# RemoteControl-v3.net
KiCad netlist of a schematic drawn in EAGLE
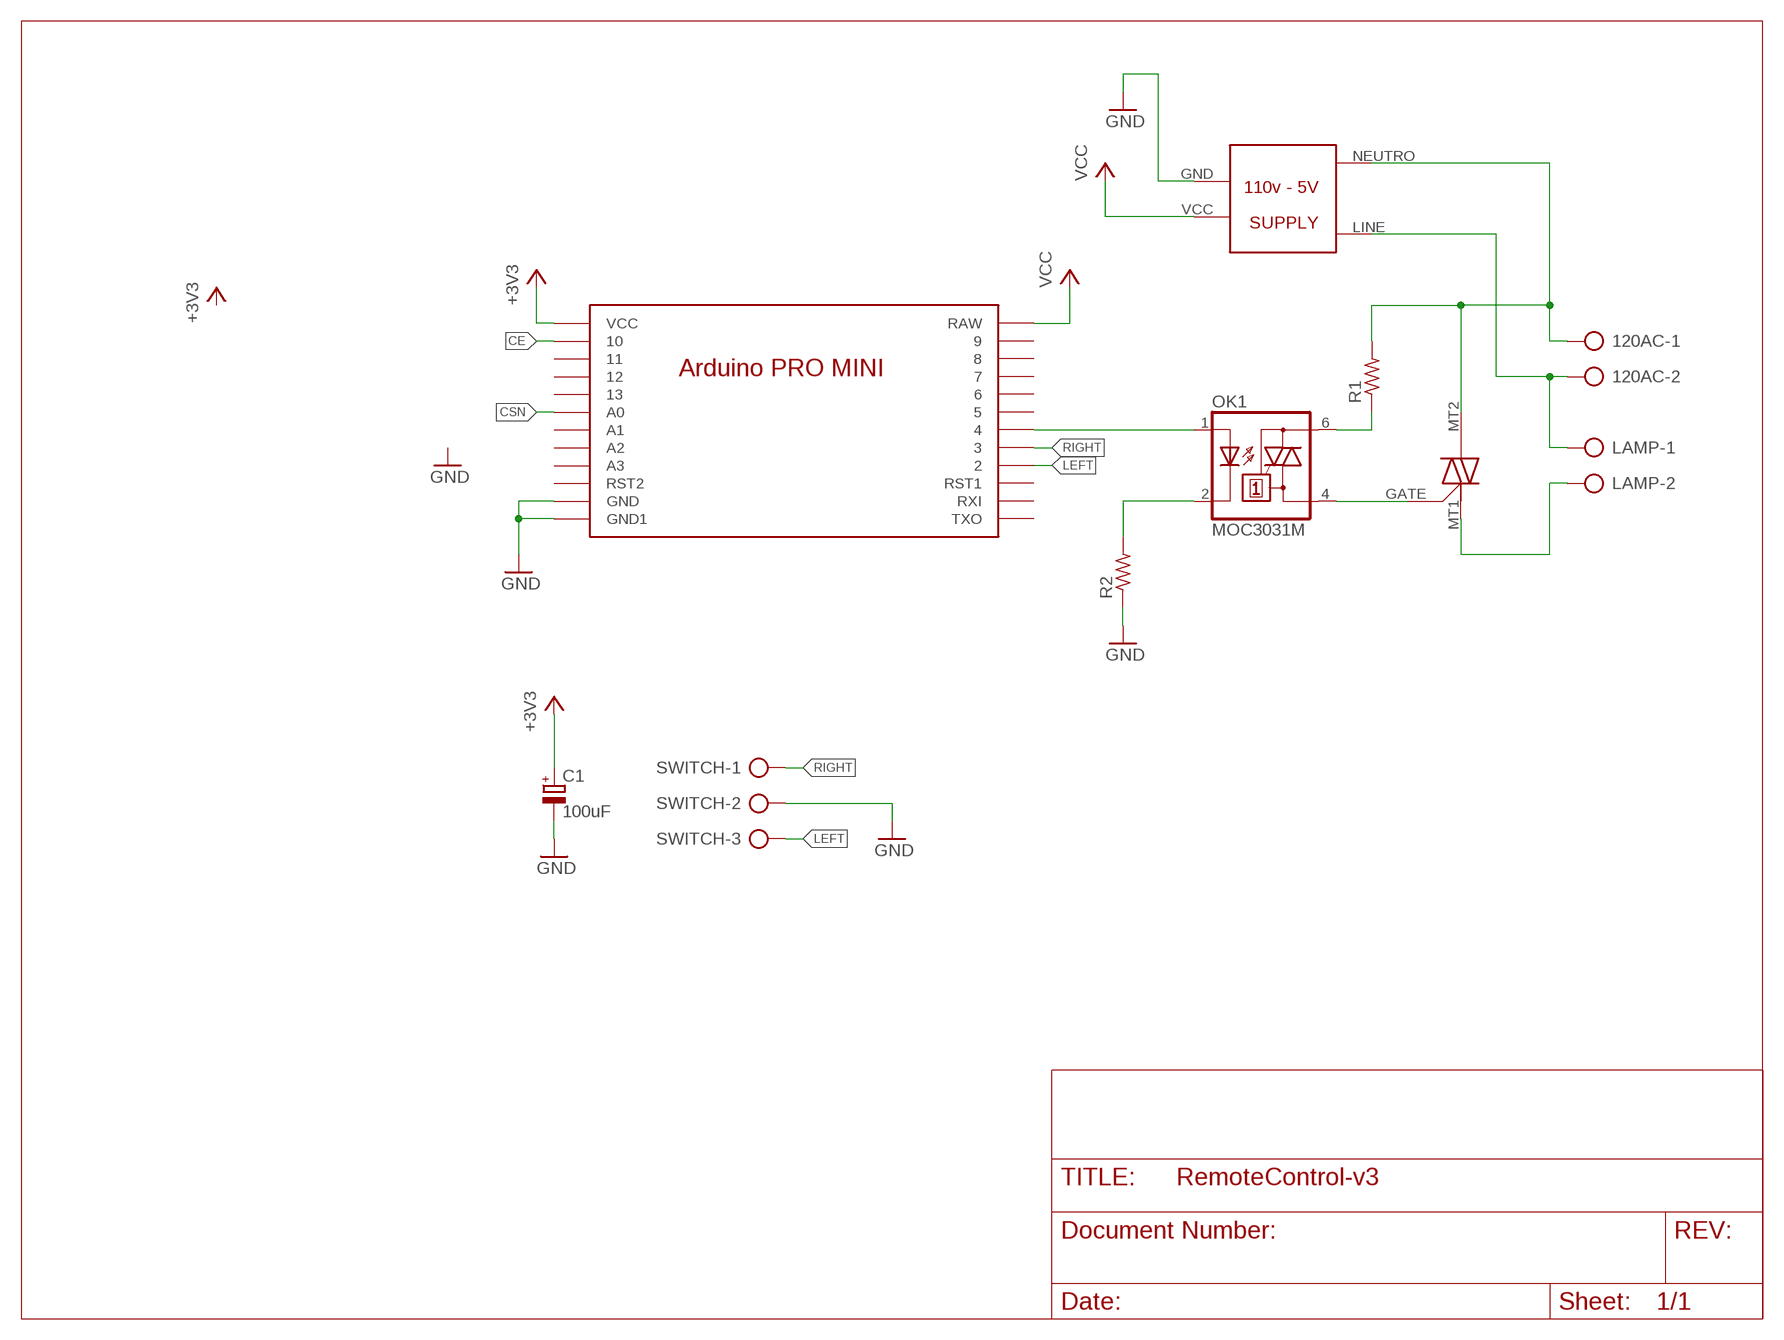
[diagram p0: schematic, sheet 1]

(export (version "E")
  (design (tool "Eeschema 10.0.6"))
  (components
    (comp (ref "120AC")
      (value "AK300/2")
      (footprint "eagle-import:AK300_2")
      (libsource (lib "eagle-import") (part "AK300/2"))
    )
    (comp (ref "C1")
      (value "100uF")
      (footprint "eagle-import:E2,5-5")
      (libsource (lib "eagle-import") (part "CPOL-EUE2.5-5"))
    )
    (comp (ref "LAMP")
      (value "AK300/2")
      (footprint "eagle-import:AK300_2")
      (libsource (lib "eagle-import") (part "AK300/2"))
    )
    (comp (ref "OK1")
      (value "MOC3031M")
      (footprint "eagle-import:DIL06")
      (fields (field (name "MF") "FAIRCHILD SEMICONDUCTOR"))
      (libsource (lib "eagle-import") (part "MOC3031M"))
    )
    (comp (ref "R1")
      (value "R-US_0204/7")
      (footprint "eagle-import:0204_7")
      (libsource (lib "eagle-import") (part "R-US_0204/7"))
    )
    (comp (ref "R2")
      (value "R-US_0204/7")
      (footprint "eagle-import:0204_7")
      (libsource (lib "eagle-import") (part "R-US_0204/7"))
    )
    (comp (ref "SWITCH")
      (value "AK300/3")
      (footprint "eagle-import:AK300_3")
      (libsource (lib "eagle-import") (part "AK300/3"))
    )
    (comp (ref "U$1")
      (value "NANO")
      (footprint "eagle-import:NANO")
      (libsource (lib "eagle-import") (part "NANO"))
    )
    (comp (ref "U$2")
      (value "MAC12")
      (footprint "eagle-import:MAC12")
      (libsource (lib "eagle-import") (part "MAC12"))
    )
    (comp (ref "U$3")
      (value "SUPPLY5V")
      (footprint "eagle-import:SUPPLY5V")
      (libsource (lib "eagle-import") (part "SUPPLY5V"))
    )
  )
  (nets
    (net (code "1") (name "+3V3") (class "Default")
      (node (ref "C1") (pin "+") (pinfunction "+_+") (pintype "passive"))
      (node (ref "U$1") (pin "VCC") (pinfunction "VCC_VCC") (pintype "bidirectional"))
    )
    (net (code "2") (name "CE") (class "Default")
      (node (ref "U$1") (pin "10") (pinfunction "10_10") (pintype "bidirectional"))
    )
    (net (code "3") (name "CSN") (class "Default")
      (node (ref "U$1") (pin "A0") (pinfunction "A0_A0") (pintype "bidirectional"))
    )
    (net (code "4") (name "GND") (class "Default")
      (node (ref "C1") (pin "-") (pinfunction "-_-") (pintype "passive"))
      (node (ref "R2") (pin "1") (pinfunction "1_1") (pintype "passive"))
      (node (ref "SWITCH") (pin "2") (pinfunction "KL_2") (pintype "passive"))
      (node (ref "U$1") (pin "GND1") (pinfunction "GND_GND1") (pintype "bidirectional"))
      (node (ref "U$1") (pin "GND2") (pinfunction "GND1_GND2") (pintype "power_in"))
      (node (ref "U$3") (pin "GND") (pinfunction "GND_GND") (pintype "bidirectional"))
    )
    (net (code "5") (name "LEFT") (class "Default")
      (node (ref "SWITCH") (pin "3") (pinfunction "KL_3") (pintype "passive"))
      (node (ref "U$1") (pin "2") (pinfunction "2_2") (pintype "bidirectional"))
    )
    (net (code "6") (name "Net-(120ACA-KL)") (class "Default")
      (node (ref "120AC") (pin "1") (pinfunction "KL_1") (pintype "passive"))
      (node (ref "R1") (pin "2") (pinfunction "2_2") (pintype "passive"))
      (node (ref "U$2") (pin "MT2") (pinfunction "MT2_MT2") (pintype "bidirectional"))
      (node (ref "U$3") (pin "NEUTRO") (pinfunction "NEUTRO_NEUTRO") (pintype "bidirectional"))
    )
    (net (code "7") (name "Net-(120ACB-KL)") (class "Default")
      (node (ref "120AC") (pin "2") (pinfunction "KL_2") (pintype "passive"))
      (node (ref "LAMP") (pin "1") (pinfunction "KL_1") (pintype "passive"))
      (node (ref "U$3") (pin "LINE") (pinfunction "LINE_LINE") (pintype "bidirectional"))
    )
    (net (code "8") (name "Net-(LAMPB-KL)") (class "Default")
      (node (ref "LAMP") (pin "2") (pinfunction "KL_2") (pintype "passive"))
      (node (ref "U$2") (pin "MT1") (pinfunction "MT1_MT1") (pintype "bidirectional"))
    )
    (net (code "9") (name "Net-(OK1-A)") (class "Default")
      (node (ref "OK1") (pin "1") (pinfunction "A_1") (pintype "passive"))
      (node (ref "U$1") (pin "4") (pinfunction "4_4") (pintype "bidirectional"))
    )
    (net (code "10") (name "Net-(OK1-A1)") (class "Default")
      (node (ref "OK1") (pin "4") (pinfunction "A1_4") (pintype "passive"))
      (node (ref "U$2") (pin "GATE") (pinfunction "GATE_GATE") (pintype "bidirectional"))
    )
    (net (code "11") (name "Net-(OK1-A2)") (class "Default")
      (node (ref "OK1") (pin "6") (pinfunction "A2_6") (pintype "passive"))
      (node (ref "R1") (pin "1") (pinfunction "1_1") (pintype "passive"))
    )
    (net (code "12") (name "Net-(OK1-C)") (class "Default")
      (node (ref "OK1") (pin "2") (pinfunction "C_2") (pintype "passive"))
      (node (ref "R2") (pin "2") (pinfunction "2_2") (pintype "passive"))
    )
    (net (code "13") (name "RIGHT") (class "Default")
      (node (ref "SWITCH") (pin "1") (pinfunction "KL_1") (pintype "passive"))
      (node (ref "U$1") (pin "3") (pinfunction "3_3") (pintype "bidirectional"))
    )
    (net (code "14") (name "VCC") (class "Default")
      (node (ref "U$1") (pin "RAW") (pinfunction "RAW_RAW") (pintype "bidirectional"))
      (node (ref "U$3") (pin "VCC") (pinfunction "VCC_VCC") (pintype "bidirectional"))
    )
    (net (code "15") (name "unconnected-(U$1-Pad5)") (class "Default")
      (node (ref "U$1") (pin "5") (pinfunction "5_5") (pintype "bidirectional"))
    )
    (net (code "16") (name "unconnected-(U$1-Pad6)") (class "Default")
      (node (ref "U$1") (pin "6") (pinfunction "6_6") (pintype "bidirectional"))
    )
    (net (code "17") (name "unconnected-(U$1-Pad7)") (class "Default")
      (node (ref "U$1") (pin "7") (pinfunction "7_7") (pintype "bidirectional"))
    )
    (net (code "18") (name "unconnected-(U$1-Pad8)") (class "Default")
      (node (ref "U$1") (pin "8") (pinfunction "8_8") (pintype "bidirectional"))
    )
    (net (code "19") (name "unconnected-(U$1-Pad9)") (class "Default")
      (node (ref "U$1") (pin "9") (pinfunction "9_9") (pintype "bidirectional"))
    )
    (net (code "20") (name "unconnected-(U$1-Pad11)") (class "Default")
      (node (ref "U$1") (pin "11") (pinfunction "11_11") (pintype "bidirectional"))
    )
    (net (code "21") (name "unconnected-(U$1-Pad12)") (class "Default")
      (node (ref "U$1") (pin "12") (pinfunction "12_12") (pintype "bidirectional"))
    )
    (net (code "22") (name "unconnected-(U$1-Pad13)") (class "Default")
      (node (ref "U$1") (pin "13") (pinfunction "13_13") (pintype "bidirectional"))
    )
    (net (code "23") (name "unconnected-(U$1-PadA1)") (class "Default")
      (node (ref "U$1") (pin "A1") (pinfunction "A1_A1") (pintype "bidirectional"))
    )
    (net (code "24") (name "unconnected-(U$1-PadA2)") (class "Default")
      (node (ref "U$1") (pin "A2") (pinfunction "A2_A2") (pintype "bidirectional"))
    )
    (net (code "25") (name "unconnected-(U$1-PadA3)") (class "Default")
      (node (ref "U$1") (pin "A3") (pinfunction "A3_A3") (pintype "bidirectional"))
    )
    (net (code "26") (name "unconnected-(U$1-PadRST1)") (class "Default")
      (node (ref "U$1") (pin "RST1") (pinfunction "RST1_RST1") (pintype "bidirectional"))
    )
    (net (code "27") (name "unconnected-(U$1-PadRST2)") (class "Default")
      (node (ref "U$1") (pin "RST2") (pinfunction "RST2_RST2") (pintype "bidirectional"))
    )
    (net (code "28") (name "unconnected-(U$1-PadRXI)") (class "Default")
      (node (ref "U$1") (pin "RXI") (pinfunction "RXI_RXI") (pintype "bidirectional"))
    )
    (net (code "29") (name "unconnected-(U$1-PadTXO)") (class "Default")
      (node (ref "U$1") (pin "TXO") (pinfunction "TXO_TXO") (pintype "bidirectional"))
    )
  )
)
